# ESP32_EIT_V3.net
KiCad netlist of a schematic drawn in EAGLE
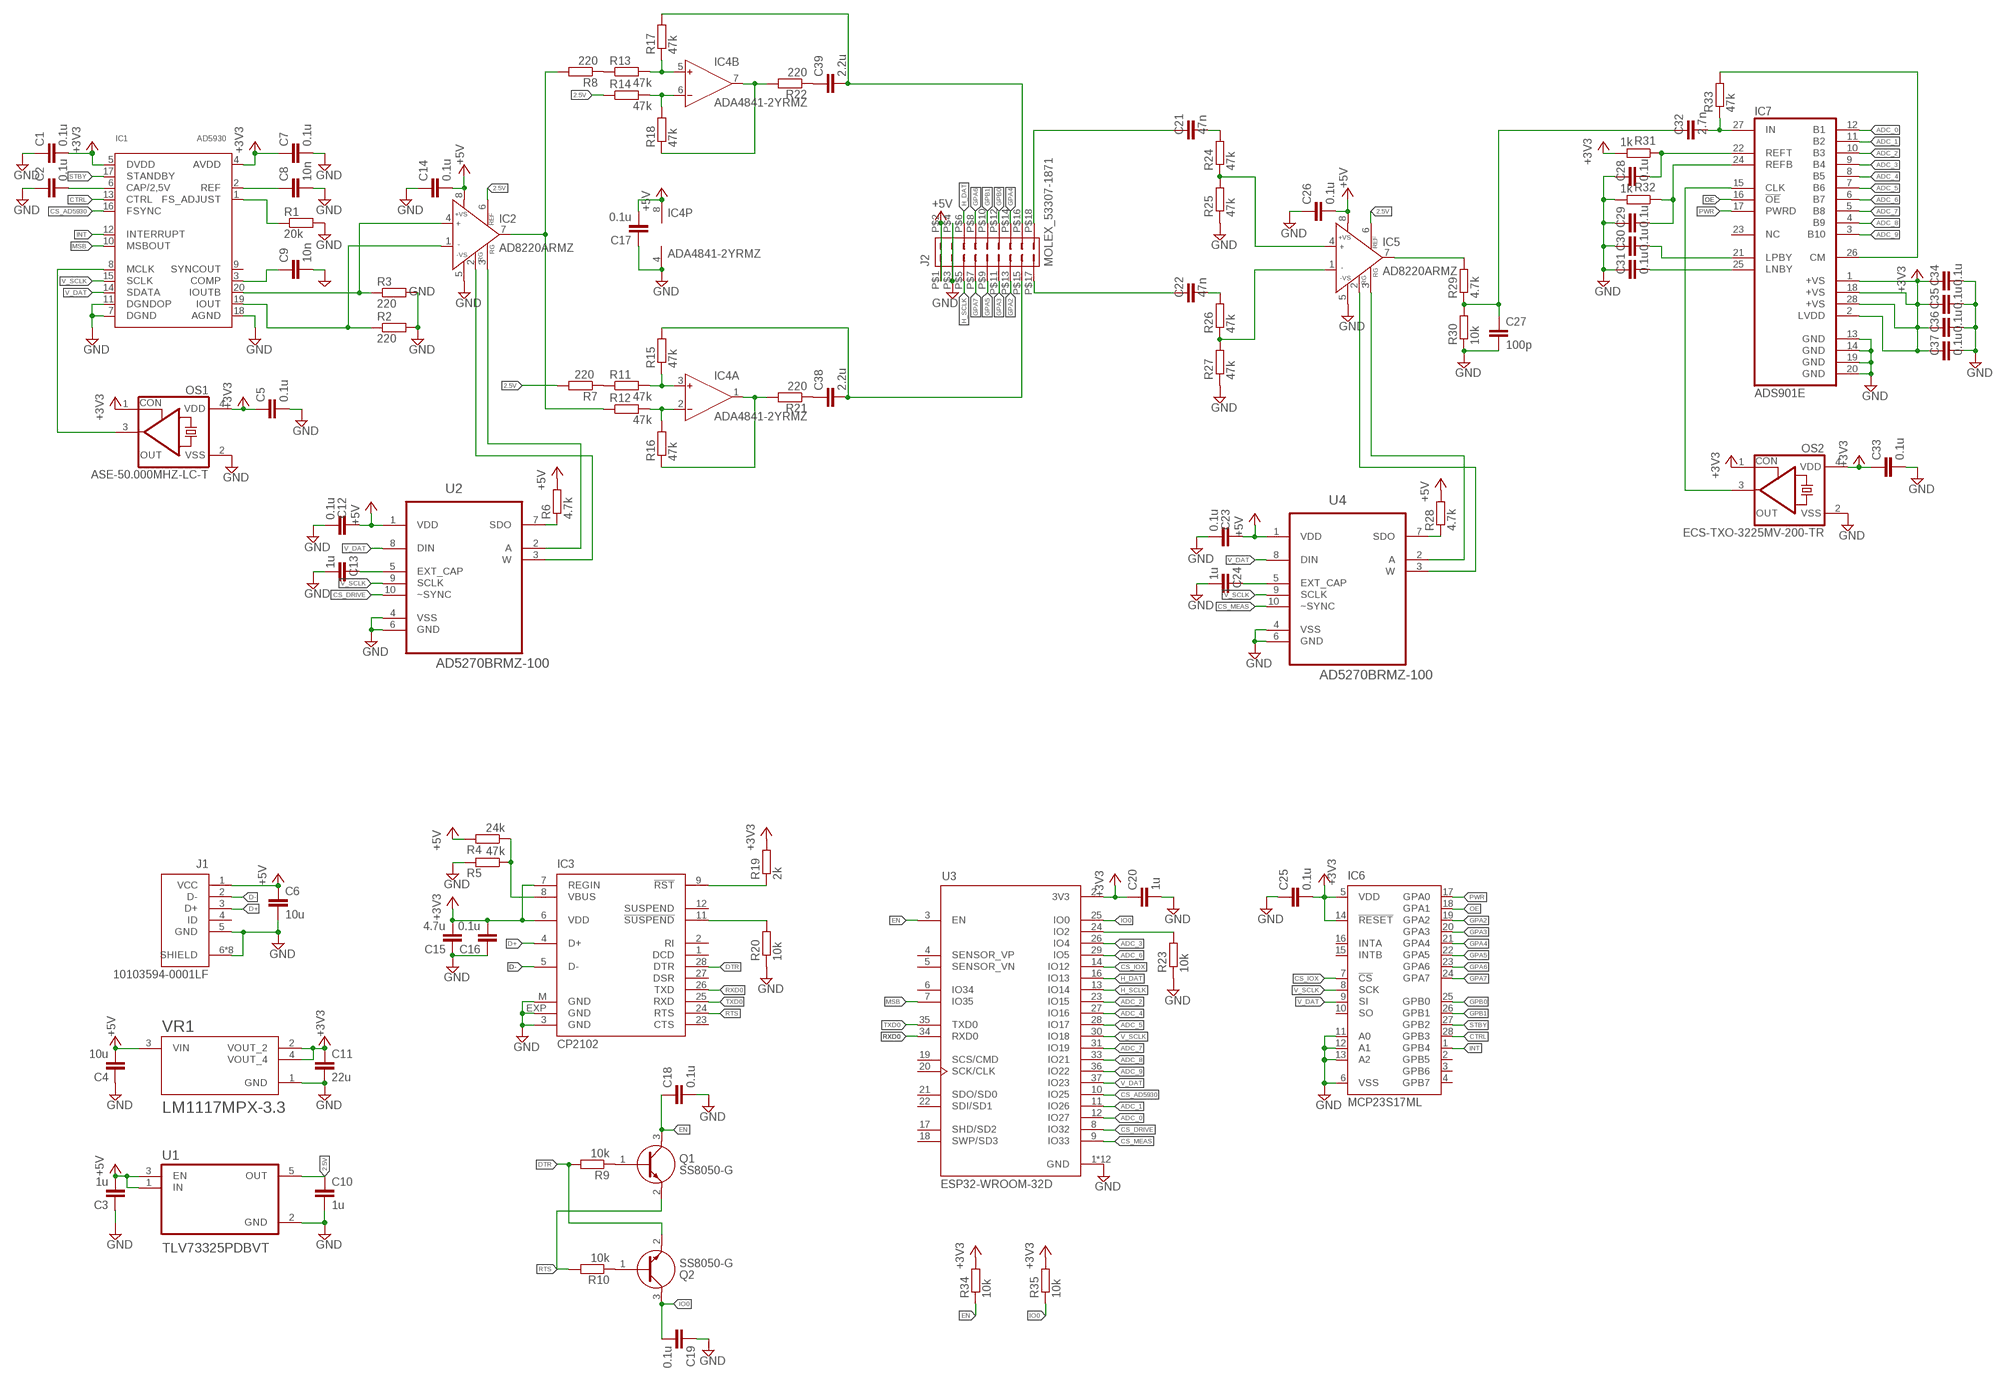
[diagram p0: schematic, sheet 1]

(export (version "E")
  (design (tool "Eeschema 10.0.6"))
  (components
    (comp (ref "C1")
      (value "0.1u")
      (footprint "eagle-import:C0603")
      (libsource (lib "eagle-import") (part "C-EUC0603"))
    )
    (comp (ref "C2")
      (value "0.1u")
      (footprint "eagle-import:C0603")
      (libsource (lib "eagle-import") (part "C-EUC0603"))
    )
    (comp (ref "C3")
      (value "1u")
      (footprint "eagle-import:C0603")
      (libsource (lib "eagle-import") (part "C-EUC0603"))
    )
    (comp (ref "C4")
      (value "10u")
      (footprint "eagle-import:C0805")
      (libsource (lib "eagle-import") (part "C-EUC0805"))
    )
    (comp (ref "C5")
      (value "0.1u")
      (footprint "eagle-import:C0603")
      (libsource (lib "eagle-import") (part "C-EUC0603"))
    )
    (comp (ref "C6")
      (value "10u")
      (footprint "eagle-import:C0805")
      (libsource (lib "eagle-import") (part "C-EUC0805"))
    )
    (comp (ref "C7")
      (value "0.1u")
      (footprint "eagle-import:C0603")
      (libsource (lib "eagle-import") (part "C-EUC0603"))
    )
    (comp (ref "C8")
      (value "10n")
      (footprint "eagle-import:C0603")
      (libsource (lib "eagle-import") (part "C-EUC0603"))
    )
    (comp (ref "C9")
      (value "10n")
      (footprint "eagle-import:C0603")
      (libsource (lib "eagle-import") (part "C-EUC0603"))
    )
    (comp (ref "C10")
      (value "1u")
      (footprint "eagle-import:C0603")
      (libsource (lib "eagle-import") (part "C-EUC0603"))
    )
    (comp (ref "C11")
      (value "22u")
      (footprint "eagle-import:C0805")
      (libsource (lib "eagle-import") (part "C-EUC0805"))
    )
    (comp (ref "C12")
      (value "0.1u")
      (footprint "eagle-import:C0603")
      (libsource (lib "eagle-import") (part "C-EUC0603"))
    )
    (comp (ref "C13")
      (value "1u")
      (footprint "eagle-import:C0603")
      (libsource (lib "eagle-import") (part "C-EUC0603"))
    )
    (comp (ref "C14")
      (value "0.1u")
      (footprint "eagle-import:C0603")
      (libsource (lib "eagle-import") (part "C-EUC0603"))
    )
    (comp (ref "C15")
      (value "4.7u")
      (footprint "eagle-import:C0603")
      (libsource (lib "eagle-import") (part "C-EUC0603"))
    )
    (comp (ref "C16")
      (value "0.1u")
      (footprint "eagle-import:C0603")
      (libsource (lib "eagle-import") (part "C-EUC0603"))
    )
    (comp (ref "C17")
      (value "0.1u")
      (footprint "eagle-import:C0603")
      (libsource (lib "eagle-import") (part "C-EUC0603"))
    )
    (comp (ref "C18")
      (value "0.1u")
      (footprint "eagle-import:C0603")
      (libsource (lib "eagle-import") (part "C-EUC0603"))
    )
    (comp (ref "C19")
      (value "0.1u")
      (footprint "eagle-import:C0603")
      (libsource (lib "eagle-import") (part "C-EUC0603"))
    )
    (comp (ref "C20")
      (value "1u")
      (footprint "eagle-import:C0603")
      (libsource (lib "eagle-import") (part "C-EUC0603"))
    )
    (comp (ref "C21")
      (value "47n")
      (footprint "eagle-import:C0603")
      (libsource (lib "eagle-import") (part "C-EUC0603"))
    )
    (comp (ref "C22")
      (value "47n")
      (footprint "eagle-import:C0603")
      (libsource (lib "eagle-import") (part "C-EUC0603"))
    )
    (comp (ref "C23")
      (value "0.1u")
      (footprint "eagle-import:C0603")
      (libsource (lib "eagle-import") (part "C-EUC0603"))
    )
    (comp (ref "C24")
      (value "1u")
      (footprint "eagle-import:C0603")
      (libsource (lib "eagle-import") (part "C-EUC0603"))
    )
    (comp (ref "C25")
      (value "0.1u")
      (footprint "eagle-import:C0603")
      (libsource (lib "eagle-import") (part "C-EUC0603"))
    )
    (comp (ref "C26")
      (value "0.1u")
      (footprint "eagle-import:C0603")
      (libsource (lib "eagle-import") (part "C-EUC0603"))
    )
    (comp (ref "C27")
      (value "100p")
      (footprint "eagle-import:C0603")
      (libsource (lib "eagle-import") (part "C-EUC0603"))
    )
    (comp (ref "C28")
      (value "0.1u")
      (footprint "eagle-import:C0603")
      (libsource (lib "eagle-import") (part "C-EUC0603"))
    )
    (comp (ref "C29")
      (value "0.1u")
      (footprint "eagle-import:C0603")
      (libsource (lib "eagle-import") (part "C-EUC0603"))
    )
    (comp (ref "C30")
      (value "0.1u")
      (footprint "eagle-import:C0603")
      (libsource (lib "eagle-import") (part "C-EUC0603"))
    )
    (comp (ref "C31")
      (value "0.1u")
      (footprint "eagle-import:C0603")
      (libsource (lib "eagle-import") (part "C-EUC0603"))
    )
    (comp (ref "C32")
      (value "2.7n")
      (footprint "eagle-import:C0603")
      (libsource (lib "eagle-import") (part "C-EUC0603"))
    )
    (comp (ref "C33")
      (value "0.1u")
      (footprint "eagle-import:C0603")
      (libsource (lib "eagle-import") (part "C-EUC0603"))
    )
    (comp (ref "C34")
      (value "0.1u")
      (footprint "eagle-import:C0603")
      (libsource (lib "eagle-import") (part "C-EUC0603"))
    )
    (comp (ref "C35")
      (value "0.1u")
      (footprint "eagle-import:C0603")
      (libsource (lib "eagle-import") (part "C-EUC0603"))
    )
    (comp (ref "C36")
      (value "0.1u")
      (footprint "eagle-import:C0603")
      (libsource (lib "eagle-import") (part "C-EUC0603"))
    )
    (comp (ref "C37")
      (value "0.1u")
      (footprint "eagle-import:C0603")
      (libsource (lib "eagle-import") (part "C-EUC0603"))
    )
    (comp (ref "C38")
      (value "2.2u")
      (footprint "eagle-import:C0603")
      (libsource (lib "eagle-import") (part "C-EUC0603"))
    )
    (comp (ref "C39")
      (value "2.2u")
      (footprint "eagle-import:C0603")
      (libsource (lib "eagle-import") (part "C-EUC0603"))
    )
    (comp (ref "IC1")
      (value "AD5930")
      (footprint "eagle-import:TSSOP20")
      (fields (field (name "MF") "Analog Devices"))
      (libsource (lib "eagle-import") (part "AD5930"))
    )
    (comp (ref "IC2")
      (value "AD8220ARMZ")
      (footprint "eagle-import:MSOP8")
      (libsource (lib "eagle-import") (part "AD8220ARMZ"))
    )
    (comp (ref "IC3")
      (value "CP2102")
      (footprint "eagle-import:MLP28")
      (fields (field (name "MF") "FARNELL") (field (name "MPN") "CP2102-GM"))
      (libsource (lib "eagle-import") (part "CP2102"))
    )
    (comp (ref "IC4")
      (value "ADA4841-2YRMZ")
      (footprint "eagle-import:MSOP8")
      (libsource (lib "eagle-import") (part "ADA4841-2YRMZ"))
    )
    (comp (ref "IC5")
      (value "AD8220ARMZ")
      (footprint "eagle-import:MSOP8")
      (libsource (lib "eagle-import") (part "AD8220ARMZ"))
    )
    (comp (ref "IC6")
      (value "MCP23S17ML")
      (footprint "eagle-import:QFN28-ML_6X6MM")
      (fields (field (name "MF") "MICROCHIP") (field (name "MPN") "MCP23S17-E/ML"))
      (libsource (lib "eagle-import") (part "MCP23S17ML"))
    )
    (comp (ref "IC7")
      (value "ADS901E")
      (footprint "eagle-import:SSOP28BU")
      (fields (field (name "MF") "TEXAS INSTRUMENT CONNECTORS"))
      (libsource (lib "eagle-import") (part "ADS901E"))
    )
    (comp (ref "J1")
      (value "10103594-0001LF")
      (footprint "eagle-import:AMPHENOL_10103594-0001LF")
      (fields (field (name "MF") "Amphenol ICC (FCI)"))
      (libsource (lib "eagle-import") (part "10103594-0001LF"))
    )
    (comp (ref "J2")
      (value "MOLEX_53307-1871")
      (footprint "eagle-import:MOLEX_53307-1871")
      (libsource (lib "eagle-import") (part "MOLEX_53307-1871"))
    )
    (comp (ref "OS1")
      (value "ASE-50.000MHZ-LC-T")
      (footprint "eagle-import:2.5X2-4-PAD")
      (libsource (lib "eagle-import") (part "OSC-OE-IQXO-793"))
    )
    (comp (ref "OS2")
      (value "ECS-TXO-3225MV-200-TR")
      (footprint "eagle-import:2.5X2-4-PAD")
      (libsource (lib "eagle-import") (part "OSC-OE-IQXO-793"))
    )
    (comp (ref "Q1")
      (value "SS8050-G")
      (footprint "eagle-import:SOT95P240X115-3N")
      (fields (field (name "MF") "Comchip Technology"))
      (libsource (lib "eagle-import") (part "SS8050-G"))
    )
    (comp (ref "Q2")
      (value "SS8050-G")
      (footprint "eagle-import:SOT95P240X115-3N")
      (fields (field (name "MF") "Comchip Technology"))
      (libsource (lib "eagle-import") (part "SS8050-G"))
    )
    (comp (ref "R1")
      (value "20k")
      (footprint "eagle-import:R0603")
      (libsource (lib "eagle-import") (part "R-EU_R0603"))
    )
    (comp (ref "R2")
      (value "220")
      (footprint "eagle-import:R0603")
      (libsource (lib "eagle-import") (part "R-EU_R0603"))
    )
    (comp (ref "R3")
      (value "220")
      (footprint "eagle-import:R0603")
      (libsource (lib "eagle-import") (part "R-EU_R0603"))
    )
    (comp (ref "R4")
      (value "24k")
      (footprint "eagle-import:R0603")
      (libsource (lib "eagle-import") (part "R-EU_R0603"))
    )
    (comp (ref "R5")
      (value "47k")
      (footprint "eagle-import:R0603")
      (libsource (lib "eagle-import") (part "R-EU_R0603"))
    )
    (comp (ref "R6")
      (value "4.7k")
      (footprint "eagle-import:R0603")
      (libsource (lib "eagle-import") (part "R-EU_R0603"))
    )
    (comp (ref "R7")
      (value "220")
      (footprint "eagle-import:R0603")
      (libsource (lib "eagle-import") (part "R-EU_R0603"))
    )
    (comp (ref "R8")
      (value "220")
      (footprint "eagle-import:R0603")
      (libsource (lib "eagle-import") (part "R-EU_R0603"))
    )
    (comp (ref "R9")
      (value "10k")
      (footprint "eagle-import:R0603")
      (libsource (lib "eagle-import") (part "R-EU_R0603"))
    )
    (comp (ref "R10")
      (value "10k")
      (footprint "eagle-import:R0603")
      (libsource (lib "eagle-import") (part "R-EU_R0603"))
    )
    (comp (ref "R11")
      (value "47k")
      (footprint "eagle-import:R0603")
      (libsource (lib "eagle-import") (part "R-EU_R0603"))
    )
    (comp (ref "R12")
      (value "47k")
      (footprint "eagle-import:R0603")
      (libsource (lib "eagle-import") (part "R-EU_R0603"))
    )
    (comp (ref "R13")
      (value "47k")
      (footprint "eagle-import:R0603")
      (libsource (lib "eagle-import") (part "R-EU_R0603"))
    )
    (comp (ref "R14")
      (value "47k")
      (footprint "eagle-import:R0603")
      (libsource (lib "eagle-import") (part "R-EU_R0603"))
    )
    (comp (ref "R15")
      (value "47k")
      (footprint "eagle-import:R0603")
      (libsource (lib "eagle-import") (part "R-EU_R0603"))
    )
    (comp (ref "R16")
      (value "47k")
      (footprint "eagle-import:R0603")
      (libsource (lib "eagle-import") (part "R-EU_R0603"))
    )
    (comp (ref "R17")
      (value "47k")
      (footprint "eagle-import:R0603")
      (libsource (lib "eagle-import") (part "R-EU_R0603"))
    )
    (comp (ref "R18")
      (value "47k")
      (footprint "eagle-import:R0603")
      (libsource (lib "eagle-import") (part "R-EU_R0603"))
    )
    (comp (ref "R19")
      (value "2k")
      (footprint "eagle-import:R0603")
      (libsource (lib "eagle-import") (part "R-EU_R0603"))
    )
    (comp (ref "R20")
      (value "10k")
      (footprint "eagle-import:R0603")
      (libsource (lib "eagle-import") (part "R-EU_R0603"))
    )
    (comp (ref "R21")
      (value "220")
      (footprint "eagle-import:R0603")
      (libsource (lib "eagle-import") (part "R-EU_R0603"))
    )
    (comp (ref "R22")
      (value "220")
      (footprint "eagle-import:R0603")
      (libsource (lib "eagle-import") (part "R-EU_R0603"))
    )
    (comp (ref "R23")
      (value "10k")
      (footprint "eagle-import:R0603")
      (libsource (lib "eagle-import") (part "R-EU_R0603"))
    )
    (comp (ref "R24")
      (value "47k")
      (footprint "eagle-import:R0603")
      (libsource (lib "eagle-import") (part "R-EU_R0603"))
    )
    (comp (ref "R25")
      (value "47k")
      (footprint "eagle-import:R0603")
      (libsource (lib "eagle-import") (part "R-EU_R0603"))
    )
    (comp (ref "R26")
      (value "47k")
      (footprint "eagle-import:R0603")
      (libsource (lib "eagle-import") (part "R-EU_R0603"))
    )
    (comp (ref "R27")
      (value "47k")
      (footprint "eagle-import:R0603")
      (libsource (lib "eagle-import") (part "R-EU_R0603"))
    )
    (comp (ref "R28")
      (value "4.7k")
      (footprint "eagle-import:R0603")
      (libsource (lib "eagle-import") (part "R-EU_R0603"))
    )
    (comp (ref "R29")
      (value "4.7k")
      (footprint "eagle-import:R0603")
      (libsource (lib "eagle-import") (part "R-EU_R0603"))
    )
    (comp (ref "R30")
      (value "10k")
      (footprint "eagle-import:R0603")
      (libsource (lib "eagle-import") (part "R-EU_R0603"))
    )
    (comp (ref "R31")
      (value "1k")
      (footprint "eagle-import:R0603")
      (libsource (lib "eagle-import") (part "R-EU_R0603"))
    )
    (comp (ref "R32")
      (value "1k")
      (footprint "eagle-import:R0603")
      (libsource (lib "eagle-import") (part "R-EU_R0603"))
    )
    (comp (ref "R33")
      (value "47k")
      (footprint "eagle-import:R0603")
      (libsource (lib "eagle-import") (part "R-EU_R0603"))
    )
    (comp (ref "R34")
      (value "10k")
      (footprint "eagle-import:R0603")
      (libsource (lib "eagle-import") (part "R-EU_R0603"))
    )
    (comp (ref "R35")
      (value "10k")
      (footprint "eagle-import:R0603")
      (libsource (lib "eagle-import") (part "R-EU_R0603"))
    )
    (comp (ref "U1")
      (value "TLV73325PDBVT")
      (footprint "eagle-import:SOT95P280X145-5N")
      (fields (field (name "MF") "Texas Instruments"))
      (libsource (lib "eagle-import") (part "TLV73325PDBVT"))
    )
    (comp (ref "U2")
      (value "AD5270BRMZ-100")
      (footprint "eagle-import:SOP50P490X110-10N")
      (fields (field (name "MF") "Analog Devices"))
      (libsource (lib "eagle-import") (part "AD5270BRMZ-100"))
    )
    (comp (ref "U3")
      (value "ESP32-WROOM-32D")
      (footprint "eagle-import:MODULE_ESP32-WROOM-32D")
      (fields (field (name "MF") "Espressif Systems"))
      (libsource (lib "eagle-import") (part "ESP32-WROOM-32D"))
    )
    (comp (ref "U4")
      (value "AD5270BRMZ-100")
      (footprint "eagle-import:SOP50P490X110-10N")
      (fields (field (name "MF") "Analog Devices"))
      (libsource (lib "eagle-import") (part "AD5270BRMZ-100"))
    )
    (comp (ref "VR1")
      (value "LM1117MPX-3.3")
      (footprint "eagle-import:VREG_LM1117MPX-3.3")
      (fields (field (name "MF") "Texas Instruments"))
      (libsource (lib "eagle-import") (part "LM1117MPX-3.3"))
    )
  )
  (nets
    (net (code "1") (name "+3V3") (class "Default")
      (node (ref "C1") (pin "2") (pinfunction "2_2") (pintype "passive"))
      (node (ref "C11") (pin "1") (pinfunction "1_1") (pintype "passive"))
      (node (ref "C15") (pin "2") (pinfunction "2_2") (pintype "passive"))
      (node (ref "C16") (pin "2") (pinfunction "2_2") (pintype "passive"))
      (node (ref "C20") (pin "1") (pinfunction "1_1") (pintype "passive"))
      (node (ref "C25") (pin "2") (pinfunction "2_2") (pintype "passive"))
      (node (ref "C33") (pin "1") (pinfunction "1_1") (pintype "passive"))
      (node (ref "C34") (pin "1") (pinfunction "1_1") (pintype "passive"))
      (node (ref "C35") (pin "1") (pinfunction "1_1") (pintype "passive"))
      (node (ref "C36") (pin "1") (pinfunction "1_1") (pintype "passive"))
      (node (ref "C37") (pin "1") (pinfunction "1_1") (pintype "passive"))
      (node (ref "C5") (pin "1") (pinfunction "1_1") (pintype "passive"))
      (node (ref "C7") (pin "1") (pinfunction "1_1") (pintype "passive"))
      (node (ref "IC1") (pin "4") (pinfunction "AVDD_4") (pintype "power_in"))
      (node (ref "IC1") (pin "5") (pinfunction "DVDD_5") (pintype "power_in"))
      (node (ref "IC3") (pin "6") (pinfunction "VDD_6") (pintype "power_in"))
      (node (ref "IC3") (pin "7") (pinfunction "REGIN_7") (pintype "passive"))
      (node (ref "IC6") (pin "14") (pinfunction "~{RESET}_14") (pintype "input"))
      (node (ref "IC6") (pin "5") (pinfunction "VDD_5") (pintype "power_in"))
      (node (ref "IC7") (pin "1") (pinfunction "+VS_1") (pintype "power_in"))
      (node (ref "IC7") (pin "18") (pinfunction "+VS_18") (pintype "power_in"))
      (node (ref "IC7") (pin "2") (pinfunction "LVDD_2") (pintype "power_in"))
      (node (ref "IC7") (pin "28") (pinfunction "+VS_28") (pintype "power_in"))
      (node (ref "OS1") (pin "1") (pinfunction "CON_1") (pintype "input"))
      (node (ref "OS1") (pin "4") (pinfunction "VDD_4") (pintype "power_in"))
      (node (ref "OS2") (pin "1") (pinfunction "CON_1") (pintype "input"))
      (node (ref "OS2") (pin "4") (pinfunction "VDD_4") (pintype "power_in"))
      (node (ref "R19") (pin "2") (pinfunction "2_2") (pintype "passive"))
      (node (ref "R31") (pin "2") (pinfunction "2_2") (pintype "passive"))
      (node (ref "R34") (pin "2") (pinfunction "2_2") (pintype "passive"))
      (node (ref "R35") (pin "2") (pinfunction "2_2") (pintype "passive"))
      (node (ref "U3") (pin "2") (pinfunction "3V3_2") (pintype "power_in"))
      (node (ref "VR1") (pin "2") (pinfunction "VOUT_2_2") (pintype "output"))
      (node (ref "VR1") (pin "4") (pinfunction "VOUT_4_4") (pintype "output"))
    )
    (net (code "2") (name "+5V") (class "Default")
      (node (ref "C12") (pin "1") (pinfunction "1_1") (pintype "passive"))
      (node (ref "C14") (pin "2") (pinfunction "2_2") (pintype "passive"))
      (node (ref "C17") (pin "2") (pinfunction "2_2") (pintype "passive"))
      (node (ref "C23") (pin "1") (pinfunction "1_1") (pintype "passive"))
      (node (ref "C26") (pin "2") (pinfunction "2_2") (pintype "passive"))
      (node (ref "C3") (pin "2") (pinfunction "2_2") (pintype "passive"))
      (node (ref "C4") (pin "2") (pinfunction "2_2") (pintype "passive"))
      (node (ref "C6") (pin "1") (pinfunction "1_1") (pintype "passive"))
      (node (ref "IC2") (pin "8") (pinfunction "+VS_8") (pintype "input"))
      (node (ref "IC4") (pin "8") (pinfunction "V+_8") (pintype "power_in"))
      (node (ref "IC5") (pin "8") (pinfunction "+VS_8") (pintype "input"))
      (node (ref "J1") (pin "1") (pinfunction "VCC_1") (pintype "power_in"))
      (node (ref "J2") (pin "P$1") (pinfunction "1_P$1") (pintype "passive"))
      (node (ref "J2") (pin "P$2") (pinfunction "2_P$2") (pintype "passive"))
      (node (ref "R28") (pin "2") (pinfunction "2_2") (pintype "passive"))
      (node (ref "R4") (pin "2") (pinfunction "2_2") (pintype "passive"))
      (node (ref "R6") (pin "2") (pinfunction "2_2") (pintype "passive"))
      (node (ref "U1") (pin "1") (pinfunction "IN_1") (pintype "input"))
      (node (ref "U1") (pin "3") (pinfunction "EN_3") (pintype "input"))
      (node (ref "U2") (pin "1") (pinfunction "VDD_1") (pintype "power_in"))
      (node (ref "U4") (pin "1") (pinfunction "VDD_1") (pintype "power_in"))
      (node (ref "VR1") (pin "3") (pinfunction "VIN_3") (pintype "input"))
    )
    (net (code "3") (name "2.5V") (class "Default")
      (node (ref "C10") (pin "1") (pinfunction "1_1") (pintype "passive"))
      (node (ref "IC2") (pin "6") (pinfunction "REF_6") (pintype "passive"))
      (node (ref "IC5") (pin "6") (pinfunction "REF_6") (pintype "passive"))
      (node (ref "R14") (pin "1") (pinfunction "1_1") (pintype "passive"))
      (node (ref "R7") (pin "2") (pinfunction "2_2") (pintype "passive"))
      (node (ref "U1") (pin "5") (pinfunction "OUT_5") (pintype "output"))
    )
    (net (code "4") (name "ADC_0") (class "Default")
      (node (ref "IC7") (pin "12") (pinfunction "B1_12") (pintype "output"))
      (node (ref "U3") (pin "12") (pinfunction "IO27_12") (pintype "bidirectional"))
    )
    (net (code "5") (name "ADC_1") (class "Default")
      (node (ref "IC7") (pin "11") (pinfunction "B2_11") (pintype "output"))
      (node (ref "U3") (pin "11") (pinfunction "IO26_11") (pintype "bidirectional"))
    )
    (net (code "6") (name "ADC_2") (class "Default")
      (node (ref "IC7") (pin "10") (pinfunction "B3_10") (pintype "output"))
      (node (ref "U3") (pin "23") (pinfunction "IO15_23") (pintype "bidirectional"))
    )
    (net (code "7") (name "ADC_3") (class "Default")
      (node (ref "IC7") (pin "9") (pinfunction "B4_9") (pintype "output"))
      (node (ref "U3") (pin "26") (pinfunction "IO4_26") (pintype "bidirectional"))
    )
    (net (code "8") (name "ADC_4") (class "Default")
      (node (ref "IC7") (pin "8") (pinfunction "B5_8") (pintype "output"))
      (node (ref "U3") (pin "27") (pinfunction "IO16_27") (pintype "bidirectional"))
    )
    (net (code "9") (name "ADC_5") (class "Default")
      (node (ref "IC7") (pin "7") (pinfunction "B6_7") (pintype "output"))
      (node (ref "U3") (pin "28") (pinfunction "IO17_28") (pintype "bidirectional"))
    )
    (net (code "10") (name "ADC_6") (class "Default")
      (node (ref "IC7") (pin "6") (pinfunction "B7_6") (pintype "output"))
      (node (ref "U3") (pin "29") (pinfunction "IO5_29") (pintype "bidirectional"))
    )
    (net (code "11") (name "ADC_7") (class "Default")
      (node (ref "IC7") (pin "5") (pinfunction "B8_5") (pintype "output"))
      (node (ref "U3") (pin "31") (pinfunction "IO19_31") (pintype "bidirectional"))
    )
    (net (code "12") (name "ADC_8") (class "Default")
      (node (ref "IC7") (pin "4") (pinfunction "B9_4") (pintype "output"))
      (node (ref "U3") (pin "33") (pinfunction "IO21_33") (pintype "bidirectional"))
    )
    (net (code "13") (name "ADC_9") (class "Default")
      (node (ref "IC7") (pin "3") (pinfunction "B10_3") (pintype "output"))
      (node (ref "U3") (pin "36") (pinfunction "IO22_36") (pintype "bidirectional"))
    )
    (net (code "14") (name "CS_AD5930") (class "Default")
      (node (ref "IC1") (pin "16") (pinfunction "FSYNC_16") (pintype "bidirectional"))
      (node (ref "U3") (pin "10") (pinfunction "IO25_10") (pintype "bidirectional"))
    )
    (net (code "15") (name "CS_DRIVE") (class "Default")
      (node (ref "U2") (pin "10") (pinfunction "~{SYNC}_10") (pintype "input"))
      (node (ref "U3") (pin "8") (pinfunction "IO32_8") (pintype "bidirectional"))
    )
    (net (code "16") (name "CS_IOX") (class "Default")
      (node (ref "IC6") (pin "7") (pinfunction "~{CS}_7") (pintype "input"))
      (node (ref "U3") (pin "14") (pinfunction "IO12_14") (pintype "bidirectional"))
    )
    (net (code "17") (name "CS_MEAS") (class "Default")
      (node (ref "U3") (pin "9") (pinfunction "IO33_9") (pintype "bidirectional"))
      (node (ref "U4") (pin "10") (pinfunction "~{SYNC}_10") (pintype "input"))
    )
    (net (code "18") (name "CTRL") (class "Default")
      (node (ref "IC1") (pin "13") (pinfunction "CTRL_13") (pintype "bidirectional"))
      (node (ref "IC6") (pin "28") (pinfunction "GPB3_28") (pintype "bidirectional"))
    )
    (net (code "19") (name "D+") (class "Default")
      (node (ref "IC3") (pin "4") (pinfunction "D+_4") (pintype "bidirectional"))
      (node (ref "J1") (pin "3") (pinfunction "D+_3") (pintype "bidirectional"))
    )
    (net (code "20") (name "D-") (class "Default")
      (node (ref "IC3") (pin "5") (pinfunction "D-_5") (pintype "bidirectional"))
      (node (ref "J1") (pin "2") (pinfunction "D-_2") (pintype "bidirectional"))
    )
    (net (code "21") (name "DTR") (class "Default")
      (node (ref "IC3") (pin "28") (pinfunction "DTR_28") (pintype "output"))
      (node (ref "Q2") (pin "2") (pinfunction "E_2") (pintype "bidirectional"))
      (node (ref "R9") (pin "2") (pinfunction "2_2") (pintype "passive"))
    )
    (net (code "22") (name "EN") (class "Default")
      (node (ref "C18") (pin "1") (pinfunction "1_1") (pintype "passive"))
      (node (ref "Q1") (pin "3") (pinfunction "C_3") (pintype "bidirectional"))
      (node (ref "R34") (pin "1") (pinfunction "1_1") (pintype "passive"))
      (node (ref "U3") (pin "3") (pinfunction "EN_3") (pintype "input"))
    )
    (net (code "23") (name "GND") (class "Default")
      (node (ref "C1") (pin "1") (pinfunction "1_1") (pintype "passive"))
      (node (ref "C10") (pin "2") (pinfunction "2_2") (pintype "passive"))
      (node (ref "C11") (pin "2") (pinfunction "2_2") (pintype "passive"))
      (node (ref "C12") (pin "2") (pinfunction "2_2") (pintype "passive"))
      (node (ref "C13") (pin "2") (pinfunction "2_2") (pintype "passive"))
      (node (ref "C14") (pin "1") (pinfunction "1_1") (pintype "passive"))
      (node (ref "C15") (pin "1") (pinfunction "1_1") (pintype "passive"))
      (node (ref "C16") (pin "1") (pinfunction "1_1") (pintype "passive"))
      (node (ref "C17") (pin "1") (pinfunction "1_1") (pintype "passive"))
      (node (ref "C18") (pin "2") (pinfunction "2_2") (pintype "passive"))
      (node (ref "C19") (pin "1") (pinfunction "1_1") (pintype "passive"))
      (node (ref "C2") (pin "1") (pinfunction "1_1") (pintype "passive"))
      (node (ref "C20") (pin "2") (pinfunction "2_2") (pintype "passive"))
      (node (ref "C23") (pin "2") (pinfunction "2_2") (pintype "passive"))
      (node (ref "C24") (pin "2") (pinfunction "2_2") (pintype "passive"))
      (node (ref "C25") (pin "1") (pinfunction "1_1") (pintype "passive"))
      (node (ref "C26") (pin "1") (pinfunction "1_1") (pintype "passive"))
      (node (ref "C27") (pin "2") (pinfunction "2_2") (pintype "passive"))
      (node (ref "C28") (pin "1") (pinfunction "1_1") (pintype "passive"))
      (node (ref "C29") (pin "1") (pinfunction "1_1") (pintype "passive"))
      (node (ref "C3") (pin "1") (pinfunction "1_1") (pintype "passive"))
      (node (ref "C30") (pin "1") (pinfunction "1_1") (pintype "passive"))
      (node (ref "C31") (pin "1") (pinfunction "1_1") (pintype "passive"))
      (node (ref "C33") (pin "2") (pinfunction "2_2") (pintype "passive"))
      (node (ref "C34") (pin "2") (pinfunction "2_2") (pintype "passive"))
      (node (ref "C35") (pin "2") (pinfunction "2_2") (pintype "passive"))
      (node (ref "C36") (pin "2") (pinfunction "2_2") (pintype "passive"))
      (node (ref "C37") (pin "2") (pinfunction "2_2") (pintype "passive"))
      (node (ref "C4") (pin "1") (pinfunction "1_1") (pintype "passive"))
      (node (ref "C5") (pin "2") (pinfunction "2_2") (pintype "passive"))
      (node (ref "C6") (pin "2") (pinfunction "2_2") (pintype "passive"))
      (node (ref "C7") (pin "2") (pinfunction "2_2") (pintype "passive"))
      (node (ref "C8") (pin "2") (pinfunction "2_2") (pintype "passive"))
      (node (ref "C9") (pin "2") (pinfunction "2_2") (pintype "passive"))
      (node (ref "IC1") (pin "11") (pinfunction "DGNDOP_11") (pintype "power_in"))
      (node (ref "IC1") (pin "18") (pinfunction "AGND_18") (pintype "power_in"))
      (node (ref "IC1") (pin "7") (pinfunction "DGND_7") (pintype "power_in"))
      (node (ref "IC2") (pin "5") (pinfunction "-VS_5") (pintype "input"))
      (node (ref "IC3") (pin "3") (pinfunction "GND_3") (pintype "power_in"))
      (node (ref "IC3") (pin "EXP") (pinfunction "GND_EXP") (pintype "power_in"))
      (node (ref "IC3") (pin "M") (pinfunction "GND_M") (pintype "power_in"))
      (node (ref "IC4") (pin "4") (pinfunction "V-_4") (pintype "power_in"))
      (node (ref "IC5") (pin "5") (pinfunction "-VS_5") (pintype "input"))
      (node (ref "IC6") (pin "11") (pinfunction "A0_11") (pintype "input"))
      (node (ref "IC6") (pin "12") (pinfunction "A1_12") (pintype "input"))
      (node (ref "IC6") (pin "13") (pinfunction "A2_13") (pintype "input"))
      (node (ref "IC6") (pin "6") (pinfunction "VSS_6") (pintype "power_in"))
      (node (ref "IC7") (pin "13") (pinfunction "GND_13") (pintype "power_in"))
      (node (ref "IC7") (pin "14") (pinfunction "GND_14") (pintype "power_in"))
      (node (ref "IC7") (pin "19") (pinfunction "GND_19") (pintype "power_in"))
      (node (ref "IC7") (pin "20") (pinfunction "GND_20") (pintype "power_in"))
      (node (ref "J1") (pin "10") (pinfunction "SHIELD_10") (pintype "passive"))
      (node (ref "J1") (pin "11") (pinfunction "SHIELD_11") (pintype "passive"))
      (node (ref "J1") (pin "5") (pinfunction "GND_5") (pintype "power_in"))
      (node (ref "J1") (pin "6") (pinfunction "SHIELD_6") (pintype "passive"))
      (node (ref "J1") (pin "7") (pinfunction "SHIELD_7") (pintype "passive"))
      (node (ref "J1") (pin "8") (pinfunction "SHIELD_8") (pintype "passive"))
      (node (ref "J1") (pin "9") (pinfunction "SHIELD_9") (pintype "passive"))
      (node (ref "J1") (pin "S1") (pinfunction "SHIELD_S1") (pintype "passive"))
      (node (ref "J1") (pin "S2") (pinfunction "SHIELD_S2") (pintype "passive"))
      (node (ref "J2") (pin "P$3") (pinfunction "3_P$3") (pintype "passive"))
      (node (ref "J2") (pin "P$4") (pinfunction "4_P$4") (pintype "passive"))
      (node (ref "OS1") (pin "2") (pinfunction "VSS_2") (pintype "power_in"))
      (node (ref "OS2") (pin "2") (pinfunction "VSS_2") (pintype "power_in"))
      (node (ref "R1") (pin "2") (pinfunction "2_2") (pintype "passive"))
      (node (ref "R2") (pin "2") (pinfunction "2_2") (pintype "passive"))
      (node (ref "R20") (pin "1") (pinfunction "1_1") (pintype "passive"))
      (node (ref "R23") (pin "1") (pinfunction "1_1") (pintype "passive"))
      (node (ref "R25") (pin "1") (pinfunction "1_1") (pintype "passive"))
      (node (ref "R27") (pin "1") (pinfunction "1_1") (pintype "passive"))
      (node (ref "R3") (pin "2") (pinfunction "2_2") (pintype "passive"))
      (node (ref "R30") (pin "1") (pinfunction "1_1") (pintype "passive"))
      (node (ref "R32") (pin "2") (pinfunction "2_2") (pintype "passive"))
      (node (ref "R5") (pin "2") (pinfunction "2_2") (pintype "passive"))
      (node (ref "U1") (pin "2") (pinfunction "GND_2") (pintype "power_in"))
      (node (ref "U2") (pin "4") (pinfunction "VSS_4") (pintype "power_in"))
      (node (ref "U2") (pin "6") (pinfunction "GND_6") (pintype "passive"))
      (node (ref "U3") (pin "1") (pinfunction "GND_1") (pintype "power_in"))
      (node (ref "U3") (pin "15") (pinfunction "GND_15") (pintype "power_in"))
      (node (ref "U3") (pin "38") (pinfunction "GND_38") (pintype "power_in"))
      (node (ref "U3") (pin "39_1") (pinfunction "GND_39_1") (pintype "power_in"))
      (node (ref "U3") (pin "39_2") (pinfunction "GND_39_2") (pintype "power_in"))
      (node (ref "U3") (pin "39_3") (pinfunction "GND_39_3") (pintype "power_in"))
      (node (ref "U3") (pin "39_4") (pinfunction "GND_39_4") (pintype "power_in"))
      (node (ref "U3") (pin "39_5") (pinfunction "GND_39_5") (pintype "power_in"))
      (node (ref "U3") (pin "39_6") (pinfunction "GND_39_6") (pintype "power_in"))
      (node (ref "U3") (pin "39_7") (pinfunction "GND_39_7") (pintype "power_in"))
      (node (ref "U3") (pin "39_8") (pinfunction "GND_39_8") (pintype "power_in"))
      (node (ref "U3") (pin "39_9") (pinfunction "GND_39_9") (pintype "power_in"))
      (node (ref "U4") (pin "4") (pinfunction "VSS_4") (pintype "power_in"))
      (node (ref "U4") (pin "6") (pinfunction "GND_6") (pintype "passive"))
      (node (ref "VR1") (pin "1") (pinfunction "GND_1") (pintype "power_in"))
    )
    (net (code "24") (name "GPA2") (class "Default")
      (node (ref "IC6") (pin "19") (pinfunction "GPA2_19") (pintype "bidirectional"))
      (node (ref "J2") (pin "P$13") (pinfunction "13_P$13") (pintype "passive"))
    )
    (net (code "25") (name "GPA3") (class "Default")
      (node (ref "IC6") (pin "20") (pinfunction "GPA3_20") (pintype "bidirectional"))
      (node (ref "J2") (pin "P$11") (pinfunction "11_P$11") (pintype "passive"))
    )
    (net (code "26") (name "GPA4") (class "Default")
      (node (ref "IC6") (pin "21") (pinfunction "GPA4_21") (pintype "bidirectional"))
      (node (ref "J2") (pin "P$14") (pinfunction "14_P$14") (pintype "passive"))
    )
    (net (code "27") (name "GPA5") (class "Default")
      (node (ref "IC6") (pin "22") (pinfunction "GPA5_22") (pintype "bidirectional"))
      (node (ref "J2") (pin "P$9") (pinfunction "9_P$9") (pintype "passive"))
    )
    (net (code "28") (name "GPA6") (class "Default")
      (node (ref "IC6") (pin "23") (pinfunction "GPA6_23") (pintype "bidirectional"))
      (node (ref "J2") (pin "P$8") (pinfunction "8_P$8") (pintype "passive"))
    )
    (net (code "29") (name "GPA7") (class "Default")
      (node (ref "IC6") (pin "24") (pinfunction "GPA7_24") (pintype "bidirectional"))
      (node (ref "J2") (pin "P$7") (pinfunction "7_P$7") (pintype "passive"))
    )
    (net (code "30") (name "GPB0") (class "Default")
      (node (ref "IC6") (pin "25") (pinfunction "GPB0_25") (pintype "bidirectional"))
      (node (ref "J2") (pin "P$12") (pinfunction "12_P$12") (pintype "passive"))
    )
    (net (code "31") (name "GPB1") (class "Default")
      (node (ref "IC6") (pin "26") (pinfunction "GPB1_26") (pintype "bidirectional"))
      (node (ref "J2") (pin "P$10") (pinfunction "10_P$10") (pintype "passive"))
    )
    (net (code "32") (name "H_DAT") (class "Default")
      (node (ref "J2") (pin "P$6") (pinfunction "6_P$6") (pintype "passive"))
      (node (ref "U3") (pin "16") (pinfunction "IO13_16") (pintype "bidirectional"))
    )
    (net (code "33") (name "H_SCLK") (class "Default")
      (node (ref "J2") (pin "P$5") (pinfunction "5_P$5") (pintype "passive"))
      (node (ref "U3") (pin "13") (pinfunction "IO14_13") (pintype "bidirectional"))
    )
    (net (code "34") (name "INT") (class "Default")
      (node (ref "IC1") (pin "12") (pinfunction "INTERRUPT_12") (pintype "bidirectional"))
      (node (ref "IC6") (pin "1") (pinfunction "GPB4_1") (pintype "bidirectional"))
    )
    (net (code "35") (name "IO0") (class "Default")
      (node (ref "C19") (pin "2") (pinfunction "2_2") (pintype "passive"))
      (node (ref "Q2") (pin "3") (pinfunction "C_3") (pintype "bidirectional"))
      (node (ref "R35") (pin "1") (pinfunction "1_1") (pintype "passive"))
      (node (ref "U3") (pin "25") (pinfunction "IO0_25") (pintype "bidirectional"))
    )
    (net (code "36") (name "MSB") (class "Default")
      (node (ref "IC1") (pin "10") (pinfunction "MSBOUT_10") (pintype "bidirectional"))
      (node (ref "U3") (pin "7") (pinfunction "IO35_7") (pintype "input"))
    )
    (net (code "37") (name "Net-(C21-Pad2)") (class "Default")
      (node (ref "C21") (pin "2") (pinfunction "2_2") (pintype "passive"))
      (node (ref "R24") (pin "2") (pinfunction "2_2") (pintype "passive"))
    )
    (net (code "38") (name "Net-(C22-Pad2)") (class "Default")
      (node (ref "C22") (pin "2") (pinfunction "2_2") (pintype "passive"))
      (node (ref "R26") (pin "2") (pinfunction "2_2") (pintype "passive"))
    )
    (net (code "39") (name "Net-(C27-Pad1)") (class "Default")
      (node (ref "C27") (pin "1") (pinfunction "1_1") (pintype "passive"))
      (node (ref "C32") (pin "1") (pinfunction "1_1") (pintype "passive"))
      (node (ref "R29") (pin "1") (pinfunction "1_1") (pintype "passive"))
      (node (ref "R30") (pin "2") (pinfunction "2_2") (pintype "passive"))
    )
    (net (code "40") (name "Net-(C38-Pad1)") (class "Default")
      (node (ref "C38") (pin "1") (pinfunction "1_1") (pintype "passive"))
      (node (ref "R21") (pin "1") (pinfunction "1_1") (pintype "passive"))
    )
    (net (code "41") (name "Net-(C39-Pad1)") (class "Default")
      (node (ref "C39") (pin "1") (pinfunction "1_1") (pintype "passive"))
      (node (ref "R22") (pin "1") (pinfunction "1_1") (pintype "passive"))
    )
    (net (code "42") (name "Net-(IC1-CAP{slash}2,5V)") (class "Default")
      (node (ref "C2") (pin "2") (pinfunction "2_2") (pintype "passive"))
      (node (ref "IC1") (pin "6") (pinfunction "CAP/2,5V_6") (pintype "bidirectional"))
    )
    (net (code "43") (name "Net-(IC1-COMP)") (class "Default")
      (node (ref "C9") (pin "1") (pinfunction "1_1") (pintype "passive"))
      (node (ref "IC1") (pin "3") (pinfunction "COMP_3") (pintype "bidirectional"))
    )
    (net (code "44") (name "Net-(IC1-FS_ADJUST)") (class "Default")
      (node (ref "IC1") (pin "1") (pinfunction "FS_ADJUST_1") (pintype "bidirectional"))
      (node (ref "R1") (pin "1") (pinfunction "1_1") (pintype "passive"))
    )
    (net (code "45") (name "Net-(IC1-IOUT)") (class "Default")
      (node (ref "IC1") (pin "19") (pinfunction "IOUT_19") (pintype "bidirectional"))
      (node (ref "IC2") (pin "1") (pinfunction "IN-_1") (pintype "input"))
      (node (ref "R2") (pin "1") (pinfunction "1_1") (pintype "passive"))
    )
    (net (code "46") (name "Net-(IC1-IOUTB)") (class "Default")
      (node (ref "IC1") (pin "20") (pinfunction "IOUTB_20") (pintype "bidirectional"))
      (node (ref "IC2") (pin "4") (pinfunction "IN+_4") (pintype "input"))
      (node (ref "R3") (pin "1") (pinfunction "1_1") (pintype "passive"))
    )
    (net (code "47") (name "Net-(IC1-MCLK)") (class "Default")
      (node (ref "IC1") (pin "8") (pinfunction "MCLK_8") (pintype "bidirectional"))
      (node (ref "OS1") (pin "3") (pinfunction "OUT_3") (pintype "output"))
    )
    (net (code "48") (name "Net-(IC1-REF)") (class "Default")
      (node (ref "C8") (pin "1") (pinfunction "1_1") (pintype "passive"))
      (node (ref "IC1") (pin "2") (pinfunction "REF_2") (pintype "bidirectional"))
    )
    (net (code "49") (name "Net-(IC2-OUT)") (class "Default")
      (node (ref "IC2") (pin "7") (pinfunction "OUT_7") (pintype "output"))
      (node (ref "R12") (pin "1") (pinfunction "1_1") (pintype "passive"))
      (node (ref "R8") (pin "2") (pinfunction "2_2") (pintype "passive"))
    )
    (net (code "50") (name "Net-(IC3-VBUS)") (class "Default")
      (node (ref "IC3") (pin "8") (pinfunction "VBUS_8") (pintype "input"))
      (node (ref "R4") (pin "1") (pinfunction "1_1") (pintype "passive"))
      (node (ref "R5") (pin "1") (pinfunction "1_1") (pintype "passive"))
    )
    (net (code "51") (name "Net-(IC3-~{RST})") (class "Default")
      (node (ref "IC3") (pin "9") (pinfunction "~{RST}_9") (pintype "bidirectional"))
      (node (ref "R19") (pin "1") (pinfunction "1_1") (pintype "passive"))
    )
    (net (code "52") (name "Net-(IC3-~{SUSPEND})") (class "Default")
      (node (ref "IC3") (pin "11") (pinfunction "~{SUSPEND}_11") (pintype "output"))
      (node (ref "R20") (pin "2") (pinfunction "2_2") (pintype "passive"))
    )
    (net (code "53") (name "Net-(IC4A-IN+)") (class "Default")
      (node (ref "IC4") (pin "3") (pinfunction "IN+_3") (pintype "input"))
      (node (ref "R11") (pin "2") (pinfunction "2_2") (pintype "passive"))
      (node (ref "R15") (pin "1") (pinfunction "1_1") (pintype "passive"))
    )
    (net (code "54") (name "Net-(IC4A-IN-)") (class "Default")
      (node (ref "IC4") (pin "2") (pinfunction "IN-_2") (pintype "input"))
      (node (ref "R12") (pin "2") (pinfunction "2_2") (pintype "passive"))
      (node (ref "R16") (pin "2") (pinfunction "2_2") (pintype "passive"))
    )
    (net (code "55") (name "Net-(IC4A-OUT)") (class "Default")
      (node (ref "IC4") (pin "1") (pinfunction "OUT_1") (pintype "output"))
      (node (ref "R16") (pin "1") (pinfunction "1_1") (pintype "passive"))
      (node (ref "R21") (pin "2") (pinfunction "2_2") (pintype "passive"))
    )
    (net (code "56") (name "Net-(IC4B-IN+)") (class "Default")
      (node (ref "IC4") (pin "5") (pinfunction "IN+_5") (pintype "input"))
      (node (ref "R13") (pin "2") (pinfunction "2_2") (pintype "passive"))
      (node (ref "R17") (pin "1") (pinfunction "1_1") (pintype "passive"))
    )
    (net (code "57") (name "Net-(IC4B-IN-)") (class "Default")
      (node (ref "IC4") (pin "6") (pinfunction "IN-_6") (pintype "input"))
      (node (ref "R14") (pin "2") (pinfunction "2_2") (pintype "passive"))
      (node (ref "R18") (pin "2") (pinfunction "2_2") (pintype "passive"))
    )
    (net (code "58") (name "Net-(IC4B-OUT)") (class "Default")
      (node (ref "IC4") (pin "7") (pinfunction "OUT_7") (pintype "output"))
      (node (ref "R18") (pin "1") (pinfunction "1_1") (pintype "passive"))
      (node (ref "R22") (pin "2") (pinfunction "2_2") (pintype "passive"))
    )
    (net (code "59") (name "Net-(IC5-IN+)") (class "Default")
      (node (ref "IC5") (pin "4") (pinfunction "IN+_4") (pintype "input"))
      (node (ref "R24") (pin "1") (pinfunction "1_1") (pintype "passive"))
      (node (ref "R25") (pin "2") (pinfunction "2_2") (pintype "passive"))
    )
    (net (code "60") (name "Net-(IC5-IN-)") (class "Default")
      (node (ref "IC5") (pin "1") (pinfunction "IN-_1") (pintype "input"))
      (node (ref "R26") (pin "1") (pinfunction "1_1") (pintype "passive"))
      (node (ref "R27") (pin "2") (pinfunction "2_2") (pintype "passive"))
    )
    (net (code "61") (name "Net-(IC5-OUT)") (class "Default")
      (node (ref "IC5") (pin "7") (pinfunction "OUT_7") (pintype "output"))
      (node (ref "R29") (pin "2") (pinfunction "2_2") (pintype "passive"))
    )
    (net (code "62") (name "Net-(IC7-CLK)") (class "Default")
      (node (ref "IC7") (pin "15") (pinfunction "CLK_15") (pintype "input"))
      (node (ref "OS2") (pin "3") (pinfunction "OUT_3") (pintype "output"))
    )
    (net (code "63") (name "Net-(IC7-CM)") (class "Default")
      (node (ref "IC7") (pin "26") (pinfunction "CM_26") (pintype "output"))
      (node (ref "R33") (pin "2") (pinfunction "2_2") (pintype "passive"))
    )
    (net (code "64") (name "Net-(IC7-IN)") (class "Default")
      (node (ref "C32") (pin "2") (pinfunction "2_2") (pintype "passive"))
      (node (ref "IC7") (pin "27") (pinfunction "IN_27") (pintype "input"))
      (node (ref "R33") (pin "1") (pinfunction "1_1") (pintype "passive"))
    )
    (net (code "65") (name "Net-(IC7-LNBY)") (class "Default")
      (node (ref "C31") (pin "2") (pinfunction "2_2") (pintype "passive"))
      (node (ref "IC7") (pin "25") (pinfunction "LNBY_25") (pintype "passive"))
    )
    (net (code "66") (name "Net-(IC7-LPBY)") (class "Default")
      (node (ref "C30") (pin "2") (pinfunction "2_2") (pintype "passive"))
      (node (ref "IC7") (pin "21") (pinfunction "LPBY_21") (pintype "passive"))
    )
    (net (code "67") (name "Net-(IC7-REFB)") (class "Default")
      (node (ref "C29") (pin "2") (pinfunction "2_2") (pintype "passive"))
      (node (ref "IC7") (pin "24") (pinfunction "REFB_24") (pintype "input"))
      (node (ref "R32") (pin "1") (pinfunction "1_1") (pintype "passive"))
    )
    (net (code "68") (name "Net-(IC7-REFT)") (class "Default")
      (node (ref "C28") (pin "2") (pinfunction "2_2") (pintype "passive"))
      (node (ref "IC7") (pin "22") (pinfunction "REFT_22") (pintype "input"))
      (node (ref "R31") (pin "1") (pinfunction "1_1") (pintype "passive"))
    )
    (net (code "69") (name "Net-(J2-15)") (class "Default")
      (node (ref "C38") (pin "2") (pinfunction "2_2") (pintype "passive"))
      (node (ref "J2") (pin "P$15") (pinfunction "15_P$15") (pintype "passive"))
      (node (ref "R15") (pin "2") (pinfunction "2_2") (pintype "passive"))
    )
    (net (code "70") (name "Net-(J2-16)") (class "Default")
      (node (ref "C39") (pin "2") (pinfunction "2_2") (pintype "passive"))
      (node (ref "J2") (pin "P$16") (pinfunction "16_P$16") (pintype "passive"))
      (node (ref "R17") (pin "2") (pinfunction "2_2") (pintype "passive"))
    )
    (net (code "71") (name "Net-(J2-17)") (class "Default")
      (node (ref "C22") (pin "1") (pinfunction "1_1") (pintype "passive"))
      (node (ref "J2") (pin "P$17") (pinfunction "17_P$17") (pintype "passive"))
    )
    (net (code "72") (name "Net-(J2-18)") (class "Default")
      (node (ref "C21") (pin "1") (pinfunction "1_1") (pintype "passive"))
      (node (ref "J2") (pin "P$18") (pinfunction "18_P$18") (pintype "passive"))
    )
    (net (code "73") (name "Net-(Q1-B)") (class "Default")
      (node (ref "Q1") (pin "1") (pinfunction "B_1") (pintype "bidirectional"))
      (node (ref "R9") (pin "1") (pinfunction "1_1") (pintype "passive"))
    )
    (net (code "74") (name "Net-(Q2-B)") (class "Default")
      (node (ref "Q2") (pin "1") (pinfunction "B_1") (pintype "bidirectional"))
      (node (ref "R10") (pin "1") (pinfunction "1_1") (pintype "passive"))
    )
    (net (code "75") (name "Net-(R11-Pad1)") (class "Default")
      (node (ref "R11") (pin "1") (pinfunction "1_1") (pintype "passive"))
      (node (ref "R7") (pin "1") (pinfunction "1_1") (pintype "passive"))
    )
    (net (code "76") (name "Net-(R13-Pad1)") (class "Default")
      (node (ref "R13") (pin "1") (pinfunction "1_1") (pintype "passive"))
      (node (ref "R8") (pin "1") (pinfunction "1_1") (pintype "passive"))
    )
    (net (code "77") (name "Net-(U2-A)") (class "Default")
      (node (ref "IC2") (pin "3") (pinfunction "RG_3") (pintype "passive"))
      (node (ref "U2") (pin "2") (pinfunction "A_2") (pintype "passive"))
    )
    (net (code "78") (name "Net-(U2-EXT_CAP)") (class "Default")
      (node (ref "C13") (pin "1") (pinfunction "1_1") (pintype "passive"))
      (node (ref "U2") (pin "5") (pinfunction "EXT_CAP_5") (pintype "passive"))
    )
    (net (code "79") (name "Net-(U2-SDO)") (class "Default")
      (node (ref "R6") (pin "1") (pinfunction "1_1") (pintype "passive"))
      (node (ref "U2") (pin "7") (pinfunction "SDO_7") (pintype "output"))
    )
    (net (code "80") (name "Net-(U2-W)") (class "Default")
      (node (ref "IC2") (pin "2") (pinfunction "RG_2") (pintype "passive"))
      (node (ref "U2") (pin "3") (pinfunction "W_3") (pintype "passive"))
    )
    (net (code "81") (name "Net-(U3-IO2)") (class "Default")
      (node (ref "R23") (pin "2") (pinfunction "2_2") (pintype "passive"))
      (node (ref "U3") (pin "24") (pinfunction "IO2_24") (pintype "bidirectional"))
    )
    (net (code "82") (name "Net-(U4-A)") (class "Default")
      (node (ref "IC5") (pin "3") (pinfunction "RG_3") (pintype "passive"))
      (node (ref "U4") (pin "2") (pinfunction "A_2") (pintype "passive"))
    )
    (net (code "83") (name "Net-(U4-EXT_CAP)") (class "Default")
      (node (ref "C24") (pin "1") (pinfunction "1_1") (pintype "passive"))
      (node (ref "U4") (pin "5") (pinfunction "EXT_CAP_5") (pintype "passive"))
    )
    (net (code "84") (name "Net-(U4-SDO)") (class "Default")
      (node (ref "R28") (pin "1") (pinfunction "1_1") (pintype "passive"))
      (node (ref "U4") (pin "7") (pinfunction "SDO_7") (pintype "output"))
    )
    (net (code "85") (name "Net-(U4-W)") (class "Default")
      (node (ref "IC5") (pin "2") (pinfunction "RG_2") (pintype "passive"))
      (node (ref "U4") (pin "3") (pinfunction "W_3") (pintype "passive"))
    )
    (net (code "86") (name "OE") (class "Default")
      (node (ref "IC6") (pin "18") (pinfunction "GPA1_18") (pintype "bidirectional"))
      (node (ref "IC7") (pin "16") (pinfunction "~{OE}_16") (pintype "input"))
    )
    (net (code "87") (name "PWR") (class "Default")
      (node (ref "IC6") (pin "17") (pinfunction "GPA0_17") (pintype "bidirectional"))
      (node (ref "IC7") (pin "17") (pinfunction "PWRD_17") (pintype "input"))
    )
    (net (code "88") (name "RTS") (class "Default")
      (node (ref "IC3") (pin "24") (pinfunction "RTS_24") (pintype "output"))
      (node (ref "Q1") (pin "2") (pinfunction "E_2") (pintype "bidirectional"))
      (node (ref "R10") (pin "2") (pinfunction "2_2") (pintype "passive"))
    )
    (net (code "89") (name "RXD0") (class "Default")
      (node (ref "IC3") (pin "26") (pinfunction "TXD_26") (pintype "output"))
      (node (ref "U3") (pin "34") (pinfunction "RXD0_34") (pintype "bidirectional"))
    )
    (net (code "90") (name "STBY") (class "Default")
      (node (ref "IC1") (pin "17") (pinfunction "STANDBY_17") (pintype "bidirectional"))
      (node (ref "IC6") (pin "27") (pinfunction "GPB2_27") (pintype "bidirectional"))
    )
    (net (code "91") (name "TXD0") (class "Default")
      (node (ref "IC3") (pin "25") (pinfunction "RXD_25") (pintype "input"))
      (node (ref "U3") (pin "35") (pinfunction "TXD0_35") (pintype "bidirectional"))
    )
    (net (code "92") (name "V_DAT") (class "Default")
      (node (ref "IC1") (pin "14") (pinfunction "SDATA_14") (pintype "bidirectional"))
      (node (ref "IC6") (pin "9") (pinfunction "SI_9") (pintype "input"))
      (node (ref "U2") (pin "8") (pinfunction "DIN_8") (pintype "input"))
      (node (ref "U3") (pin "37") (pinfunction "IO23_37") (pintype "bidirectional"))
      (node (ref "U4") (pin "8") (pinfunction "DIN_8") (pintype "input"))
    )
    (net (code "93") (name "V_SCLK") (class "Default")
      (node (ref "IC1") (pin "15") (pinfunction "SCLK_15") (pintype "bidirectional"))
      (node (ref "IC6") (pin "8") (pinfunction "SCK_8") (pintype "input"))
      (node (ref "U2") (pin "9") (pinfunction "SCLK_9") (pintype "input"))
      (node (ref "U3") (pin "30") (pinfunction "IO18_30") (pintype "bidirectional"))
      (node (ref "U4") (pin "9") (pinfunction "SCLK_9") (pintype "input"))
    )
    (net (code "94") (name "unconnected-(IC1-SYNCOUT-Pad9)") (class "Default")
      (node (ref "IC1") (pin "9") (pinfunction "SYNCOUT_9") (pintype "bidirectional"))
    )
    (net (code "95") (name "unconnected-(IC3-CTS-Pad23)") (class "Default")
      (node (ref "IC3") (pin "23") (pinfunction "CTS_23") (pintype "input"))
    )
    (net (code "96") (name "unconnected-(IC3-DCD-Pad1)") (class "Default")
      (node (ref "IC3") (pin "1") (pinfunction "DCD_1") (pintype "input"))
    )
    (net (code "97") (name "unconnected-(IC3-DSR-Pad27)") (class "Default")
      (node (ref "IC3") (pin "27") (pinfunction "DSR_27") (pintype "input"))
    )
    (net (code "98") (name "unconnected-(IC3-RI-Pad2)") (class "Default")
      (node (ref "IC3") (pin "2") (pinfunction "RI_2") (pintype "input"))
    )
    (net (code "99") (name "unconnected-(IC3-SUSPEND-Pad12)") (class "Default")
      (node (ref "IC3") (pin "12") (pinfunction "SUSPEND_12") (pintype "output"))
    )
    (net (code "100") (name "unconnected-(IC6-GPB5-Pad2)") (class "Default")
      (node (ref "IC6") (pin "2") (pinfunction "GPB5_2") (pintype "bidirectional"))
    )
    (net (code "101") (name "unconnected-(IC6-GPB6-Pad3)") (class "Default")
      (node (ref "IC6") (pin "3") (pinfunction "GPB6_3") (pintype "bidirectional"))
    )
    (net (code "102") (name "unconnected-(IC6-GPB7-Pad4)") (class "Default")
      (node (ref "IC6") (pin "4") (pinfunction "GPB7_4") (pintype "bidirectional"))
    )
    (net (code "103") (name "unconnected-(IC6-INTA-Pad16)") (class "Default")
      (node (ref "IC6") (pin "16") (pinfunction "INTA_16") (pintype "output"))
    )
    (net (code "104") (name "unconnected-(IC6-INTB-Pad15)") (class "Default")
      (node (ref "IC6") (pin "15") (pinfunction "INTB_15") (pintype "output"))
    )
    (net (code "105") (name "unconnected-(IC6-SO-Pad10)") (class "Default")
      (node (ref "IC6") (pin "10") (pinfunction "SO_10") (pintype "output"))
    )
    (net (code "106") (name "unconnected-(IC7-NC-Pad23)") (class "Default")
      (node (ref "IC7") (pin "23") (pinfunction "NC_23") (pintype "no_connect"))
    )
    (net (code "107") (name "unconnected-(J1-ID-Pad4)") (class "Default")
      (node (ref "J1") (pin "4") (pinfunction "ID_4") (pintype "bidirectional"))
    )
    (net (code "108") (name "unconnected-(U3-IO34-Pad6)") (class "Default")
      (node (ref "U3") (pin "6") (pinfunction "IO34_6") (pintype "input"))
    )
    (net (code "109") (name "unconnected-(U3-SCK{slash}CLK-Pad20)") (class "Default")
      (node (ref "U3") (pin "20") (pinfunction "SCK/CLK_20") (pintype "bidirectional"))
    )
    (net (code "110") (name "unconnected-(U3-SCS{slash}CMD-Pad19)") (class "Default")
      (node (ref "U3") (pin "19") (pinfunction "SCS/CMD_19") (pintype "bidirectional"))
    )
    (net (code "111") (name "unconnected-(U3-SDI{slash}SD1-Pad22)") (class "Default")
      (node (ref "U3") (pin "22") (pinfunction "SDI/SD1_22") (pintype "bidirectional"))
    )
    (net (code "112") (name "unconnected-(U3-SDO{slash}SD0-Pad21)") (class "Default")
      (node (ref "U3") (pin "21") (pinfunction "SDO/SD0_21") (pintype "bidirectional"))
    )
    (net (code "113") (name "unconnected-(U3-SENSOR_VN-Pad5)") (class "Default")
      (node (ref "U3") (pin "5") (pinfunction "SENSOR_VN_5") (pintype "input"))
    )
    (net (code "114") (name "unconnected-(U3-SENSOR_VP-Pad4)") (class "Default")
      (node (ref "U3") (pin "4") (pinfunction "SENSOR_VP_4") (pintype "input"))
    )
    (net (code "115") (name "unconnected-(U3-SHD{slash}SD2-Pad17)") (class "Default")
      (node (ref "U3") (pin "17") (pinfunction "SHD/SD2_17") (pintype "bidirectional"))
    )
    (net (code "116") (name "unconnected-(U3-SWP{slash}SD3-Pad18)") (class "Default")
      (node (ref "U3") (pin "18") (pinfunction "SWP/SD3_18") (pintype "bidirectional"))
    )
  )
)
